# In-Out.net
KiCad netlist of a schematic drawn in Altium Designer
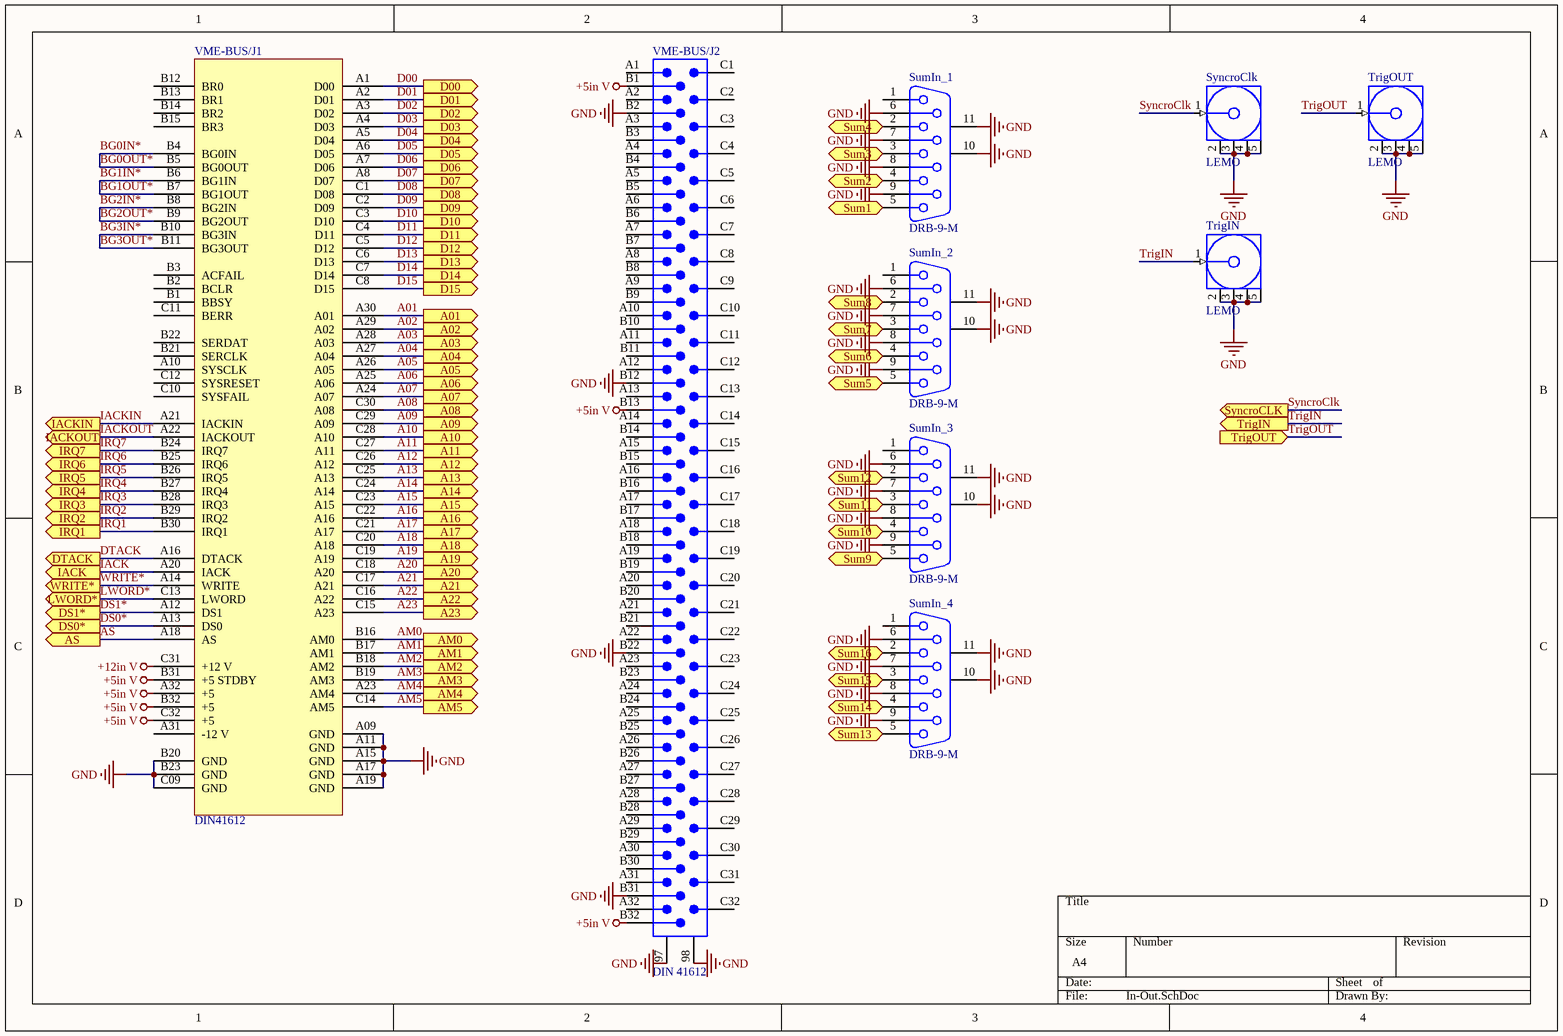
[diagram p0: In-Out.SchDoc]

(export (version "E")
  (design (tool "Eeschema 10.0.6"))
  (components
    (comp (ref "SumIn_1")
      (value "DRB-9-M")
      (footprint "DSUB1.385-2H9")
      (description "Receptacle Assembly, 9 Position, Right Angle")
      (fields (field (name "PUBLISHER") "Altium Limited"))
      (libsource (lib "Miscellaneous Connectors") (part "D Connector 9"))
    )
    (comp (ref "SumIn_2")
      (value "DRB-9-M")
      (footprint "DSUB1.385-2H9")
      (description "Receptacle Assembly, 9 Position, Right Angle")
      (fields (field (name "PUBLISHER") "Altium Limited"))
      (libsource (lib "Miscellaneous Connectors") (part "D Connector 9"))
    )
    (comp (ref "SumIn_3")
      (value "DRB-9-M")
      (footprint "DSUB1.385-2H9")
      (description "Receptacle Assembly, 9 Position, Right Angle")
      (fields (field (name "PUBLISHER") "Altium Limited"))
      (libsource (lib "Miscellaneous Connectors") (part "D Connector 9"))
    )
    (comp (ref "SumIn_4")
      (value "DRB-9-M")
      (footprint "DSUB1.385-2H9")
      (description "Receptacle Assembly, 9 Position, Right Angle")
      (fields (field (name "PUBLISHER") "Altium Limited"))
      (libsource (lib "Miscellaneous Connectors") (part "D Connector 9"))
    )
    (comp (ref "SyncroClk")
      (value "LEMO")
      (footprint "LEMO")
      (fields (field (name "PUBLISHER") "Altium Limited"))
      (libsource (lib "Miscellaneous Connectors") (part "COAX-F"))
    )
    (comp (ref "TrigIN")
      (value "LEMO")
      (footprint "LEMO")
      (fields (field (name "PUBLISHER") "Altium Limited"))
      (libsource (lib "Miscellaneous Connectors") (part "COAX-F"))
    )
    (comp (ref "TrigOUT")
      (value "LEMO")
      (footprint "LEMO")
      (fields (field (name "PUBLISHER") "Altium Limited"))
      (libsource (lib "Miscellaneous Connectors") (part "COAX-F"))
    )
    (comp (ref "VME-BUS/J1")
      (value "DIN41612")
      (footprint "Con DIN 41612:EURO2.54-2H96")
      (libsource (lib "vDevice") (part "VME-P1/J1"))
    )
    (comp (ref "VME-BUS/J2")
      (value "DIN 41612")
      (footprint "EURO2.54-2H96")
      (description "96-Pin Connector (3x32 2.54mm grid)")
      (libsource (lib "*") (part "CNVME96"))
    )
  )
  (nets
    (net (code "1") (name "+5in V") (class "Default")
      (node (ref "VME-BUS/J1") (pin "A32") (pinfunction "+5_A32") (pintype "passive"))
      (node (ref "VME-BUS/J1") (pin "B31") (pinfunction "+5_STDBY_B31") (pintype "passive"))
      (node (ref "VME-BUS/J1") (pin "B32") (pinfunction "+5_B32") (pintype "passive"))
      (node (ref "VME-BUS/J1") (pin "C32") (pinfunction "+5_C32") (pintype "passive"))
      (node (ref "VME-BUS/J2") (pin "B1") (pinfunction "B1_B1") (pintype "passive"))
      (node (ref "VME-BUS/J2") (pin "B13") (pinfunction "B13_B13") (pintype "passive"))
      (node (ref "VME-BUS/J2") (pin "B32") (pinfunction "B32_B32") (pintype "passive"))
    )
    (net (code "2") (name "+12in V") (class "Default")
      (node (ref "VME-BUS/J1") (pin "C31") (pinfunction "+12_V_C31") (pintype "passive"))
    )
    (net (code "3") (name "/A01") (class "Default")
      (node (ref "VME-BUS/J1") (pin "A30") (pinfunction "A01_A30") (pintype "passive"))
    )
    (net (code "4") (name "/A02") (class "Default")
      (node (ref "VME-BUS/J1") (pin "A29") (pinfunction "A02_A29") (pintype "passive"))
    )
    (net (code "5") (name "/A03") (class "Default")
      (node (ref "VME-BUS/J1") (pin "A28") (pinfunction "A03_A28") (pintype "passive"))
    )
    (net (code "6") (name "/A04") (class "Default")
      (node (ref "VME-BUS/J1") (pin "A27") (pinfunction "A04_A27") (pintype "passive"))
    )
    (net (code "7") (name "/A05") (class "Default")
      (node (ref "VME-BUS/J1") (pin "A26") (pinfunction "A05_A26") (pintype "passive"))
    )
    (net (code "8") (name "/A06") (class "Default")
      (node (ref "VME-BUS/J1") (pin "A25") (pinfunction "A06_A25") (pintype "passive"))
    )
    (net (code "9") (name "/A07") (class "Default")
      (node (ref "VME-BUS/J1") (pin "A24") (pinfunction "A07_A24") (pintype "passive"))
    )
    (net (code "10") (name "/A08") (class "Default")
      (node (ref "VME-BUS/J1") (pin "C30") (pinfunction "A08_C30") (pintype "passive"))
    )
    (net (code "11") (name "/A09") (class "Default")
      (node (ref "VME-BUS/J1") (pin "C29") (pinfunction "A09_C29") (pintype "passive"))
    )
    (net (code "12") (name "/A10") (class "Default")
      (node (ref "VME-BUS/J1") (pin "C28") (pinfunction "A10_C28") (pintype "passive"))
    )
    (net (code "13") (name "/A11") (class "Default")
      (node (ref "VME-BUS/J1") (pin "C27") (pinfunction "A11_C27") (pintype "passive"))
    )
    (net (code "14") (name "/A12") (class "Default")
      (node (ref "VME-BUS/J1") (pin "C26") (pinfunction "A12_C26") (pintype "passive"))
    )
    (net (code "15") (name "/A13") (class "Default")
      (node (ref "VME-BUS/J1") (pin "C25") (pinfunction "A13_C25") (pintype "passive"))
    )
    (net (code "16") (name "/A14") (class "Default")
      (node (ref "VME-BUS/J1") (pin "C24") (pinfunction "A14_C24") (pintype "passive"))
    )
    (net (code "17") (name "/A15") (class "Default")
      (node (ref "VME-BUS/J1") (pin "C23") (pinfunction "A15_C23") (pintype "passive"))
    )
    (net (code "18") (name "/A16") (class "Default")
      (node (ref "VME-BUS/J1") (pin "C22") (pinfunction "A16_C22") (pintype "passive"))
    )
    (net (code "19") (name "/A17") (class "Default")
      (node (ref "VME-BUS/J1") (pin "C21") (pinfunction "A17_C21") (pintype "passive"))
    )
    (net (code "20") (name "/A18") (class "Default")
      (node (ref "VME-BUS/J1") (pin "C20") (pinfunction "A18_C20") (pintype "passive"))
    )
    (net (code "21") (name "/A19") (class "Default")
      (node (ref "VME-BUS/J1") (pin "C19") (pinfunction "A19_C19") (pintype "passive"))
    )
    (net (code "22") (name "/A20") (class "Default")
      (node (ref "VME-BUS/J1") (pin "C18") (pinfunction "A20_C18") (pintype "passive"))
    )
    (net (code "23") (name "/A21") (class "Default")
      (node (ref "VME-BUS/J1") (pin "C17") (pinfunction "A21_C17") (pintype "passive"))
    )
    (net (code "24") (name "/A22") (class "Default")
      (node (ref "VME-BUS/J1") (pin "C16") (pinfunction "A22_C16") (pintype "passive"))
    )
    (net (code "25") (name "/A23") (class "Default")
      (node (ref "VME-BUS/J1") (pin "C15") (pinfunction "A23_C15") (pintype "passive"))
    )
    (net (code "26") (name "/AM0") (class "Default")
      (node (ref "VME-BUS/J1") (pin "B16") (pinfunction "AM0_B16") (pintype "passive"))
    )
    (net (code "27") (name "/AM1") (class "Default")
      (node (ref "VME-BUS/J1") (pin "B17") (pinfunction "AM1_B17") (pintype "passive"))
    )
    (net (code "28") (name "/AM2") (class "Default")
      (node (ref "VME-BUS/J1") (pin "B18") (pinfunction "AM2_B18") (pintype "passive"))
    )
    (net (code "29") (name "/AM3") (class "Default")
      (node (ref "VME-BUS/J1") (pin "B19") (pinfunction "AM3_B19") (pintype "passive"))
    )
    (net (code "30") (name "/AM4") (class "Default")
      (node (ref "VME-BUS/J1") (pin "A23") (pinfunction "AM4_A23") (pintype "passive"))
    )
    (net (code "31") (name "/AM5") (class "Default")
      (node (ref "VME-BUS/J1") (pin "C14") (pinfunction "AM5_C14") (pintype "passive"))
    )
    (net (code "32") (name "/AS") (class "Default")
      (node (ref "VME-BUS/J1") (pin "A18") (pinfunction "AS_A18") (pintype "passive"))
    )
    (net (code "33") (name "/BG0IN*") (class "Default")
      (node (ref "VME-BUS/J1") (pin "B4") (pinfunction "BG0IN_B4") (pintype "passive"))
      (node (ref "VME-BUS/J1") (pin "B5") (pinfunction "BG0OUT_B5") (pintype "passive"))
    )
    (net (code "34") (name "/BG1IN*") (class "Default")
      (node (ref "VME-BUS/J1") (pin "B6") (pinfunction "BG1IN_B6") (pintype "passive"))
      (node (ref "VME-BUS/J1") (pin "B7") (pinfunction "BG1OUT_B7") (pintype "passive"))
    )
    (net (code "35") (name "/BG2IN*") (class "Default")
      (node (ref "VME-BUS/J1") (pin "B8") (pinfunction "BG2IN_B8") (pintype "passive"))
      (node (ref "VME-BUS/J1") (pin "B9") (pinfunction "BG2OUT_B9") (pintype "passive"))
    )
    (net (code "36") (name "/BG3IN*") (class "Default")
      (node (ref "VME-BUS/J1") (pin "B10") (pinfunction "BG3IN_B10") (pintype "passive"))
      (node (ref "VME-BUS/J1") (pin "B11") (pinfunction "BG3OUT_B11") (pintype "passive"))
    )
    (net (code "37") (name "/D00") (class "Default")
      (node (ref "VME-BUS/J1") (pin "A1") (pinfunction "D00_A1") (pintype "passive"))
    )
    (net (code "38") (name "/D01") (class "Default")
      (node (ref "VME-BUS/J1") (pin "A2") (pinfunction "D01_A2") (pintype "passive"))
    )
    (net (code "39") (name "/D02") (class "Default")
      (node (ref "VME-BUS/J1") (pin "A3") (pinfunction "D02_A3") (pintype "passive"))
    )
    (net (code "40") (name "/D03") (class "Default")
      (node (ref "VME-BUS/J1") (pin "A4") (pinfunction "D03_A4") (pintype "passive"))
    )
    (net (code "41") (name "/D04") (class "Default")
      (node (ref "VME-BUS/J1") (pin "A5") (pinfunction "D04_A5") (pintype "passive"))
    )
    (net (code "42") (name "/D05") (class "Default")
      (node (ref "VME-BUS/J1") (pin "A6") (pinfunction "D05_A6") (pintype "passive"))
    )
    (net (code "43") (name "/D06") (class "Default")
      (node (ref "VME-BUS/J1") (pin "A7") (pinfunction "D06_A7") (pintype "passive"))
    )
    (net (code "44") (name "/D07") (class "Default")
      (node (ref "VME-BUS/J1") (pin "A8") (pinfunction "D07_A8") (pintype "passive"))
    )
    (net (code "45") (name "/D08") (class "Default")
      (node (ref "VME-BUS/J1") (pin "C1") (pinfunction "D08_C1") (pintype "passive"))
    )
    (net (code "46") (name "/D09") (class "Default")
      (node (ref "VME-BUS/J1") (pin "C2") (pinfunction "D09_C2") (pintype "passive"))
    )
    (net (code "47") (name "/D10") (class "Default")
      (node (ref "VME-BUS/J1") (pin "C3") (pinfunction "D10_C3") (pintype "passive"))
    )
    (net (code "48") (name "/D11") (class "Default")
      (node (ref "VME-BUS/J1") (pin "C4") (pinfunction "D11_C4") (pintype "passive"))
    )
    (net (code "49") (name "/D12") (class "Default")
      (node (ref "VME-BUS/J1") (pin "C5") (pinfunction "D12_C5") (pintype "passive"))
    )
    (net (code "50") (name "/D13") (class "Default")
      (node (ref "VME-BUS/J1") (pin "C6") (pinfunction "D13_C6") (pintype "passive"))
    )
    (net (code "51") (name "/D14") (class "Default")
      (node (ref "VME-BUS/J1") (pin "C7") (pinfunction "D14_C7") (pintype "passive"))
    )
    (net (code "52") (name "/D15") (class "Default")
      (node (ref "VME-BUS/J1") (pin "C8") (pinfunction "D15_C8") (pintype "passive"))
    )
    (net (code "53") (name "/DS0*") (class "Default")
      (node (ref "VME-BUS/J1") (pin "A13") (pinfunction "DS0_A13") (pintype "passive"))
    )
    (net (code "54") (name "/DS1*") (class "Default")
      (node (ref "VME-BUS/J1") (pin "A12") (pinfunction "DS1_A12") (pintype "passive"))
    )
    (net (code "55") (name "/DTACK") (class "Default")
      (node (ref "VME-BUS/J1") (pin "A16") (pinfunction "DTACK_A16") (pintype "passive"))
    )
    (net (code "56") (name "/IACK") (class "Default")
      (node (ref "VME-BUS/J1") (pin "A20") (pinfunction "IACK_A20") (pintype "passive"))
    )
    (net (code "57") (name "/IACKIN") (class "Default")
      (node (ref "VME-BUS/J1") (pin "A21") (pinfunction "IACKIN_A21") (pintype "passive"))
    )
    (net (code "58") (name "/IACKOUT") (class "Default")
      (node (ref "VME-BUS/J1") (pin "A22") (pinfunction "IACKOUT_A22") (pintype "passive"))
    )
    (net (code "59") (name "/IRQ1") (class "Default")
      (node (ref "VME-BUS/J1") (pin "B30") (pinfunction "IRQ1_B30") (pintype "passive"))
    )
    (net (code "60") (name "/IRQ2") (class "Default")
      (node (ref "VME-BUS/J1") (pin "B29") (pinfunction "IRQ2_B29") (pintype "passive"))
    )
    (net (code "61") (name "/IRQ3") (class "Default")
      (node (ref "VME-BUS/J1") (pin "B28") (pinfunction "IRQ3_B28") (pintype "passive"))
    )
    (net (code "62") (name "/IRQ4") (class "Default")
      (node (ref "VME-BUS/J1") (pin "B27") (pinfunction "IRQ4_B27") (pintype "passive"))
    )
    (net (code "63") (name "/IRQ5") (class "Default")
      (node (ref "VME-BUS/J1") (pin "B26") (pinfunction "IRQ5_B26") (pintype "passive"))
    )
    (net (code "64") (name "/IRQ6") (class "Default")
      (node (ref "VME-BUS/J1") (pin "B25") (pinfunction "IRQ6_B25") (pintype "passive"))
    )
    (net (code "65") (name "/IRQ7") (class "Default")
      (node (ref "VME-BUS/J1") (pin "B24") (pinfunction "IRQ7_B24") (pintype "passive"))
    )
    (net (code "66") (name "/LWORD*") (class "Default")
      (node (ref "VME-BUS/J1") (pin "C13") (pinfunction "LWORD_C13") (pintype "passive"))
    )
    (net (code "67") (name "/Sum1") (class "Default")
      (node (ref "SumIn_1") (pin "5") (pinfunction "5_5") (pintype "passive"))
    )
    (net (code "68") (name "/Sum2") (class "Default")
      (node (ref "SumIn_1") (pin "4") (pinfunction "4_4") (pintype "passive"))
    )
    (net (code "69") (name "/Sum3") (class "Default")
      (node (ref "SumIn_1") (pin "3") (pinfunction "3_3") (pintype "passive"))
    )
    (net (code "70") (name "/Sum4") (class "Default")
      (node (ref "SumIn_1") (pin "2") (pinfunction "2_2") (pintype "passive"))
    )
    (net (code "71") (name "/Sum5") (class "Default")
      (node (ref "SumIn_2") (pin "5") (pinfunction "5_5") (pintype "passive"))
    )
    (net (code "72") (name "/Sum6") (class "Default")
      (node (ref "SumIn_2") (pin "4") (pinfunction "4_4") (pintype "passive"))
    )
    (net (code "73") (name "/Sum7") (class "Default")
      (node (ref "SumIn_2") (pin "3") (pinfunction "3_3") (pintype "passive"))
    )
    (net (code "74") (name "/Sum8") (class "Default")
      (node (ref "SumIn_2") (pin "2") (pinfunction "2_2") (pintype "passive"))
    )
    (net (code "75") (name "/Sum9") (class "Default")
      (node (ref "SumIn_3") (pin "5") (pinfunction "5_5") (pintype "passive"))
    )
    (net (code "76") (name "/Sum10") (class "Default")
      (node (ref "SumIn_3") (pin "4") (pinfunction "4_4") (pintype "passive"))
    )
    (net (code "77") (name "/Sum11") (class "Default")
      (node (ref "SumIn_3") (pin "3") (pinfunction "3_3") (pintype "passive"))
    )
    (net (code "78") (name "/Sum12") (class "Default")
      (node (ref "SumIn_3") (pin "2") (pinfunction "2_2") (pintype "passive"))
    )
    (net (code "79") (name "/Sum13") (class "Default")
      (node (ref "SumIn_4") (pin "5") (pinfunction "5_5") (pintype "passive"))
    )
    (net (code "80") (name "/Sum14") (class "Default")
      (node (ref "SumIn_4") (pin "4") (pinfunction "4_4") (pintype "passive"))
    )
    (net (code "81") (name "/Sum15") (class "Default")
      (node (ref "SumIn_4") (pin "3") (pinfunction "3_3") (pintype "passive"))
    )
    (net (code "82") (name "/Sum16") (class "Default")
      (node (ref "SumIn_4") (pin "2") (pinfunction "2_2") (pintype "passive"))
    )
    (net (code "83") (name "/SyncroClk") (class "Default")
      (node (ref "SyncroClk") (pin "1") (pinfunction "Signal_1") (pintype "input"))
    )
    (net (code "84") (name "/TrigIN") (class "Default")
      (node (ref "TrigIN") (pin "1") (pinfunction "Signal_1") (pintype "input"))
    )
    (net (code "85") (name "/TrigOUT") (class "Default")
      (node (ref "TrigOUT") (pin "1") (pinfunction "Signal_1") (pintype "input"))
    )
    (net (code "86") (name "/WRITE*") (class "Default")
      (node (ref "VME-BUS/J1") (pin "A14") (pinfunction "WRITE_A14") (pintype "passive"))
    )
    (net (code "87") (name "GND") (class "Default")
      (node (ref "SumIn_1") (pin "10") (pinfunction "MH1_10") (pintype "passive"))
      (node (ref "SumIn_1") (pin "11") (pinfunction "MH2_11") (pintype "passive"))
      (node (ref "SumIn_1") (pin "6") (pinfunction "6_6") (pintype "passive"))
      (node (ref "SumIn_1") (pin "7") (pinfunction "7_7") (pintype "passive"))
      (node (ref "SumIn_1") (pin "8") (pinfunction "8_8") (pintype "passive"))
      (node (ref "SumIn_1") (pin "9") (pinfunction "9_9") (pintype "passive"))
      (node (ref "SumIn_2") (pin "10") (pinfunction "MH1_10") (pintype "passive"))
      (node (ref "SumIn_2") (pin "11") (pinfunction "MH2_11") (pintype "passive"))
      (node (ref "SumIn_2") (pin "6") (pinfunction "6_6") (pintype "passive"))
      (node (ref "SumIn_2") (pin "7") (pinfunction "7_7") (pintype "passive"))
      (node (ref "SumIn_2") (pin "8") (pinfunction "8_8") (pintype "passive"))
      (node (ref "SumIn_2") (pin "9") (pinfunction "9_9") (pintype "passive"))
      (node (ref "SumIn_3") (pin "10") (pinfunction "MH1_10") (pintype "passive"))
      (node (ref "SumIn_3") (pin "11") (pinfunction "MH2_11") (pintype "passive"))
      (node (ref "SumIn_3") (pin "6") (pinfunction "6_6") (pintype "passive"))
      (node (ref "SumIn_3") (pin "7") (pinfunction "7_7") (pintype "passive"))
      (node (ref "SumIn_3") (pin "8") (pinfunction "8_8") (pintype "passive"))
      (node (ref "SumIn_3") (pin "9") (pinfunction "9_9") (pintype "passive"))
      (node (ref "SumIn_4") (pin "10") (pinfunction "MH1_10") (pintype "passive"))
      (node (ref "SumIn_4") (pin "11") (pinfunction "MH2_11") (pintype "passive"))
      (node (ref "SumIn_4") (pin "6") (pinfunction "6_6") (pintype "passive"))
      (node (ref "SumIn_4") (pin "7") (pinfunction "7_7") (pintype "passive"))
      (node (ref "SumIn_4") (pin "8") (pinfunction "8_8") (pintype "passive"))
      (node (ref "SumIn_4") (pin "9") (pinfunction "9_9") (pintype "passive"))
      (node (ref "SyncroClk") (pin "2") (pinfunction "GND_2") (pintype "power_in"))
      (node (ref "SyncroClk") (pin "3") (pinfunction "GND_3") (pintype "power_in"))
      (node (ref "SyncroClk") (pin "4") (pinfunction "GND_4") (pintype "power_in"))
      (node (ref "SyncroClk") (pin "5") (pinfunction "GND_5") (pintype "power_in"))
      (node (ref "TrigIN") (pin "2") (pinfunction "GND_2") (pintype "power_in"))
      (node (ref "TrigIN") (pin "3") (pinfunction "GND_3") (pintype "power_in"))
      (node (ref "TrigIN") (pin "4") (pinfunction "GND_4") (pintype "power_in"))
      (node (ref "TrigIN") (pin "5") (pinfunction "GND_5") (pintype "power_in"))
      (node (ref "TrigOUT") (pin "2") (pinfunction "GND_2") (pintype "power_in"))
      (node (ref "TrigOUT") (pin "3") (pinfunction "GND_3") (pintype "power_in"))
      (node (ref "TrigOUT") (pin "4") (pinfunction "GND_4") (pintype "power_in"))
      (node (ref "TrigOUT") (pin "5") (pinfunction "GND_5") (pintype "power_in"))
      (node (ref "VME-BUS/J1") (pin "A09") (pinfunction "GND_A09") (pintype "passive"))
      (node (ref "VME-BUS/J1") (pin "A11") (pinfunction "GND_A11") (pintype "passive"))
      (node (ref "VME-BUS/J1") (pin "A15") (pinfunction "GND_A15") (pintype "passive"))
      (node (ref "VME-BUS/J1") (pin "A17") (pinfunction "GND_A17") (pintype "passive"))
      (node (ref "VME-BUS/J1") (pin "A19") (pinfunction "GND_A19") (pintype "passive"))
      (node (ref "VME-BUS/J1") (pin "B20") (pinfunction "GND_B20") (pintype "passive"))
      (node (ref "VME-BUS/J1") (pin "B23") (pinfunction "GND_B23") (pintype "passive"))
      (node (ref "VME-BUS/J1") (pin "C09") (pinfunction "GND_C09") (pintype "passive"))
      (node (ref "VME-BUS/J2") (pin "97") (pinfunction "97_97") (pintype "passive"))
      (node (ref "VME-BUS/J2") (pin "98") (pinfunction "98_98") (pintype "passive"))
      (node (ref "VME-BUS/J2") (pin "B12") (pinfunction "B12_B12") (pintype "passive"))
      (node (ref "VME-BUS/J2") (pin "B2") (pinfunction "B2_B2") (pintype "passive"))
      (node (ref "VME-BUS/J2") (pin "B22") (pinfunction "B22_B22") (pintype "passive"))
      (node (ref "VME-BUS/J2") (pin "B31") (pinfunction "B31_B31") (pintype "passive"))
    )
    (net (code "88") (name "unconnected-(SumIn_1-Pad1)") (class "Default")
      (node (ref "SumIn_1") (pin "1") (pinfunction "1_1") (pintype "passive"))
    )
    (net (code "89") (name "unconnected-(SumIn_2-Pad1)") (class "Default")
      (node (ref "SumIn_2") (pin "1") (pinfunction "1_1") (pintype "passive"))
    )
    (net (code "90") (name "unconnected-(SumIn_3-Pad1)") (class "Default")
      (node (ref "SumIn_3") (pin "1") (pinfunction "1_1") (pintype "passive"))
    )
    (net (code "91") (name "unconnected-(SumIn_4-Pad1)") (class "Default")
      (node (ref "SumIn_4") (pin "1") (pinfunction "1_1") (pintype "passive"))
    )
    (net (code "92") (name "unconnected-(VME-BUS/J1--12_V-PadA31)") (class "Default")
      (node (ref "VME-BUS/J1") (pin "A31") (pinfunction "-12_V_A31") (pintype "passive"))
    )
    (net (code "93") (name "unconnected-(VME-BUS/J1-ACFAIL-PadB3)") (class "Default")
      (node (ref "VME-BUS/J1") (pin "B3") (pinfunction "ACFAIL_B3") (pintype "passive"))
    )
    (net (code "94") (name "unconnected-(VME-BUS/J1-BBSY-PadB1)") (class "Default")
      (node (ref "VME-BUS/J1") (pin "B1") (pinfunction "BBSY_B1") (pintype "passive"))
    )
    (net (code "95") (name "unconnected-(VME-BUS/J1-BCLR-PadB2)") (class "Default")
      (node (ref "VME-BUS/J1") (pin "B2") (pinfunction "BCLR_B2") (pintype "passive"))
    )
    (net (code "96") (name "unconnected-(VME-BUS/J1-BERR-PadC11)") (class "Default")
      (node (ref "VME-BUS/J1") (pin "C11") (pinfunction "BERR_C11") (pintype "passive"))
    )
    (net (code "97") (name "unconnected-(VME-BUS/J1-BR0-PadB12)") (class "Default")
      (node (ref "VME-BUS/J1") (pin "B12") (pinfunction "BR0_B12") (pintype "passive"))
    )
    (net (code "98") (name "unconnected-(VME-BUS/J1-BR1-PadB13)") (class "Default")
      (node (ref "VME-BUS/J1") (pin "B13") (pinfunction "BR1_B13") (pintype "passive"))
    )
    (net (code "99") (name "unconnected-(VME-BUS/J1-BR2-PadB14)") (class "Default")
      (node (ref "VME-BUS/J1") (pin "B14") (pinfunction "BR2_B14") (pintype "passive"))
    )
    (net (code "100") (name "unconnected-(VME-BUS/J1-BR3-PadB15)") (class "Default")
      (node (ref "VME-BUS/J1") (pin "B15") (pinfunction "BR3_B15") (pintype "passive"))
    )
    (net (code "101") (name "unconnected-(VME-BUS/J1-SERCLK-PadB21)") (class "Default")
      (node (ref "VME-BUS/J1") (pin "B21") (pinfunction "SERCLK_B21") (pintype "passive"))
    )
    (net (code "102") (name "unconnected-(VME-BUS/J1-SERDAT-PadB22)") (class "Default")
      (node (ref "VME-BUS/J1") (pin "B22") (pinfunction "SERDAT_B22") (pintype "passive"))
    )
    (net (code "103") (name "unconnected-(VME-BUS/J1-SYSCLK-PadA10)") (class "Default")
      (node (ref "VME-BUS/J1") (pin "A10") (pinfunction "SYSCLK_A10") (pintype "passive"))
    )
    (net (code "104") (name "unconnected-(VME-BUS/J1-SYSFAIL-PadC10)") (class "Default")
      (node (ref "VME-BUS/J1") (pin "C10") (pinfunction "SYSFAIL_C10") (pintype "passive"))
    )
    (net (code "105") (name "unconnected-(VME-BUS/J1-SYSRESET-PadC12)") (class "Default")
      (node (ref "VME-BUS/J1") (pin "C12") (pinfunction "SYSRESET_C12") (pintype "passive"))
    )
    (net (code "106") (name "unconnected-(VME-BUS/J2-PadA1)") (class "Default")
      (node (ref "VME-BUS/J2") (pin "A1") (pinfunction "A1_A1") (pintype "passive"))
    )
    (net (code "107") (name "unconnected-(VME-BUS/J2-PadA2)") (class "Default")
      (node (ref "VME-BUS/J2") (pin "A2") (pinfunction "A2_A2") (pintype "passive"))
    )
    (net (code "108") (name "unconnected-(VME-BUS/J2-PadA3)") (class "Default")
      (node (ref "VME-BUS/J2") (pin "A3") (pinfunction "A3_A3") (pintype "passive"))
    )
    (net (code "109") (name "unconnected-(VME-BUS/J2-PadA4)") (class "Default")
      (node (ref "VME-BUS/J2") (pin "A4") (pinfunction "A4_A4") (pintype "passive"))
    )
    (net (code "110") (name "unconnected-(VME-BUS/J2-PadA5)") (class "Default")
      (node (ref "VME-BUS/J2") (pin "A5") (pinfunction "A5_A5") (pintype "passive"))
    )
    (net (code "111") (name "unconnected-(VME-BUS/J2-PadA6)") (class "Default")
      (node (ref "VME-BUS/J2") (pin "A6") (pinfunction "A6_A6") (pintype "passive"))
    )
    (net (code "112") (name "unconnected-(VME-BUS/J2-PadA7)") (class "Default")
      (node (ref "VME-BUS/J2") (pin "A7") (pinfunction "A7_A7") (pintype "passive"))
    )
    (net (code "113") (name "unconnected-(VME-BUS/J2-PadA8)") (class "Default")
      (node (ref "VME-BUS/J2") (pin "A8") (pinfunction "A8_A8") (pintype "passive"))
    )
    (net (code "114") (name "unconnected-(VME-BUS/J2-PadA9)") (class "Default")
      (node (ref "VME-BUS/J2") (pin "A9") (pinfunction "A9_A9") (pintype "passive"))
    )
    (net (code "115") (name "unconnected-(VME-BUS/J2-PadA10)") (class "Default")
      (node (ref "VME-BUS/J2") (pin "A10") (pinfunction "A10_A10") (pintype "passive"))
    )
    (net (code "116") (name "unconnected-(VME-BUS/J2-PadA11)") (class "Default")
      (node (ref "VME-BUS/J2") (pin "A11") (pinfunction "A11_A11") (pintype "passive"))
    )
    (net (code "117") (name "unconnected-(VME-BUS/J2-PadA12)") (class "Default")
      (node (ref "VME-BUS/J2") (pin "A12") (pinfunction "A12_A12") (pintype "passive"))
    )
    (net (code "118") (name "unconnected-(VME-BUS/J2-PadA13)") (class "Default")
      (node (ref "VME-BUS/J2") (pin "A13") (pinfunction "A13_A13") (pintype "passive"))
    )
    (net (code "119") (name "unconnected-(VME-BUS/J2-PadA14)") (class "Default")
      (node (ref "VME-BUS/J2") (pin "A14") (pinfunction "A14_A14") (pintype "passive"))
    )
    (net (code "120") (name "unconnected-(VME-BUS/J2-PadA15)") (class "Default")
      (node (ref "VME-BUS/J2") (pin "A15") (pinfunction "A15_A15") (pintype "passive"))
    )
    (net (code "121") (name "unconnected-(VME-BUS/J2-PadA16)") (class "Default")
      (node (ref "VME-BUS/J2") (pin "A16") (pinfunction "A16_A16") (pintype "passive"))
    )
    (net (code "122") (name "unconnected-(VME-BUS/J2-PadA17)") (class "Default")
      (node (ref "VME-BUS/J2") (pin "A17") (pinfunction "A17_A17") (pintype "passive"))
    )
    (net (code "123") (name "unconnected-(VME-BUS/J2-PadA18)") (class "Default")
      (node (ref "VME-BUS/J2") (pin "A18") (pinfunction "A18_A18") (pintype "passive"))
    )
    (net (code "124") (name "unconnected-(VME-BUS/J2-PadA19)") (class "Default")
      (node (ref "VME-BUS/J2") (pin "A19") (pinfunction "A19_A19") (pintype "passive"))
    )
    (net (code "125") (name "unconnected-(VME-BUS/J2-PadA20)") (class "Default")
      (node (ref "VME-BUS/J2") (pin "A20") (pinfunction "A20_A20") (pintype "passive"))
    )
    (net (code "126") (name "unconnected-(VME-BUS/J2-PadA21)") (class "Default")
      (node (ref "VME-BUS/J2") (pin "A21") (pinfunction "A21_A21") (pintype "passive"))
    )
    (net (code "127") (name "unconnected-(VME-BUS/J2-PadA22)") (class "Default")
      (node (ref "VME-BUS/J2") (pin "A22") (pinfunction "A22_A22") (pintype "passive"))
    )
    (net (code "128") (name "unconnected-(VME-BUS/J2-PadA23)") (class "Default")
      (node (ref "VME-BUS/J2") (pin "A23") (pinfunction "A23_A23") (pintype "passive"))
    )
    (net (code "129") (name "unconnected-(VME-BUS/J2-PadA24)") (class "Default")
      (node (ref "VME-BUS/J2") (pin "A24") (pinfunction "A24_A24") (pintype "passive"))
    )
    (net (code "130") (name "unconnected-(VME-BUS/J2-PadA25)") (class "Default")
      (node (ref "VME-BUS/J2") (pin "A25") (pinfunction "A25_A25") (pintype "passive"))
    )
    (net (code "131") (name "unconnected-(VME-BUS/J2-PadA26)") (class "Default")
      (node (ref "VME-BUS/J2") (pin "A26") (pinfunction "A26_A26") (pintype "passive"))
    )
    (net (code "132") (name "unconnected-(VME-BUS/J2-PadA27)") (class "Default")
      (node (ref "VME-BUS/J2") (pin "A27") (pinfunction "A27_A27") (pintype "passive"))
    )
    (net (code "133") (name "unconnected-(VME-BUS/J2-PadA28)") (class "Default")
      (node (ref "VME-BUS/J2") (pin "A28") (pinfunction "A28_A28") (pintype "passive"))
    )
    (net (code "134") (name "unconnected-(VME-BUS/J2-PadA29)") (class "Default")
      (node (ref "VME-BUS/J2") (pin "A29") (pinfunction "A29_A29") (pintype "passive"))
    )
    (net (code "135") (name "unconnected-(VME-BUS/J2-PadA30)") (class "Default")
      (node (ref "VME-BUS/J2") (pin "A30") (pinfunction "A30_A30") (pintype "passive"))
    )
    (net (code "136") (name "unconnected-(VME-BUS/J2-PadA31)") (class "Default")
      (node (ref "VME-BUS/J2") (pin "A31") (pinfunction "A31_A31") (pintype "passive"))
    )
    (net (code "137") (name "unconnected-(VME-BUS/J2-PadA32)") (class "Default")
      (node (ref "VME-BUS/J2") (pin "A32") (pinfunction "A32_A32") (pintype "passive"))
    )
    (net (code "138") (name "unconnected-(VME-BUS/J2-PadB3)") (class "Default")
      (node (ref "VME-BUS/J2") (pin "B3") (pinfunction "B3_B3") (pintype "passive"))
    )
    (net (code "139") (name "unconnected-(VME-BUS/J2-PadB4)") (class "Default")
      (node (ref "VME-BUS/J2") (pin "B4") (pinfunction "B4_B4") (pintype "passive"))
    )
    (net (code "140") (name "unconnected-(VME-BUS/J2-PadB5)") (class "Default")
      (node (ref "VME-BUS/J2") (pin "B5") (pinfunction "B5_B5") (pintype "passive"))
    )
    (net (code "141") (name "unconnected-(VME-BUS/J2-PadB6)") (class "Default")
      (node (ref "VME-BUS/J2") (pin "B6") (pinfunction "B6_B6") (pintype "passive"))
    )
    (net (code "142") (name "unconnected-(VME-BUS/J2-PadB7)") (class "Default")
      (node (ref "VME-BUS/J2") (pin "B7") (pinfunction "B7_B7") (pintype "passive"))
    )
    (net (code "143") (name "unconnected-(VME-BUS/J2-PadB8)") (class "Default")
      (node (ref "VME-BUS/J2") (pin "B8") (pinfunction "B8_B8") (pintype "passive"))
    )
    (net (code "144") (name "unconnected-(VME-BUS/J2-PadB9)") (class "Default")
      (node (ref "VME-BUS/J2") (pin "B9") (pinfunction "B9_B9") (pintype "passive"))
    )
    (net (code "145") (name "unconnected-(VME-BUS/J2-PadB10)") (class "Default")
      (node (ref "VME-BUS/J2") (pin "B10") (pinfunction "B10_B10") (pintype "passive"))
    )
    (net (code "146") (name "unconnected-(VME-BUS/J2-PadB11)") (class "Default")
      (node (ref "VME-BUS/J2") (pin "B11") (pinfunction "B11_B11") (pintype "passive"))
    )
    (net (code "147") (name "unconnected-(VME-BUS/J2-PadB14)") (class "Default")
      (node (ref "VME-BUS/J2") (pin "B14") (pinfunction "B14_B14") (pintype "passive"))
    )
    (net (code "148") (name "unconnected-(VME-BUS/J2-PadB15)") (class "Default")
      (node (ref "VME-BUS/J2") (pin "B15") (pinfunction "B15_B15") (pintype "passive"))
    )
    (net (code "149") (name "unconnected-(VME-BUS/J2-PadB16)") (class "Default")
      (node (ref "VME-BUS/J2") (pin "B16") (pinfunction "B16_B16") (pintype "passive"))
    )
    (net (code "150") (name "unconnected-(VME-BUS/J2-PadB17)") (class "Default")
      (node (ref "VME-BUS/J2") (pin "B17") (pinfunction "B17_B17") (pintype "passive"))
    )
    (net (code "151") (name "unconnected-(VME-BUS/J2-PadB18)") (class "Default")
      (node (ref "VME-BUS/J2") (pin "B18") (pinfunction "B18_B18") (pintype "passive"))
    )
    (net (code "152") (name "unconnected-(VME-BUS/J2-PadB19)") (class "Default")
      (node (ref "VME-BUS/J2") (pin "B19") (pinfunction "B19_B19") (pintype "passive"))
    )
    (net (code "153") (name "unconnected-(VME-BUS/J2-PadB20)") (class "Default")
      (node (ref "VME-BUS/J2") (pin "B20") (pinfunction "B20_B20") (pintype "passive"))
    )
    (net (code "154") (name "unconnected-(VME-BUS/J2-PadB21)") (class "Default")
      (node (ref "VME-BUS/J2") (pin "B21") (pinfunction "B21_B21") (pintype "passive"))
    )
    (net (code "155") (name "unconnected-(VME-BUS/J2-PadB23)") (class "Default")
      (node (ref "VME-BUS/J2") (pin "B23") (pinfunction "B23_B23") (pintype "passive"))
    )
    (net (code "156") (name "unconnected-(VME-BUS/J2-PadB24)") (class "Default")
      (node (ref "VME-BUS/J2") (pin "B24") (pinfunction "B24_B24") (pintype "passive"))
    )
    (net (code "157") (name "unconnected-(VME-BUS/J2-PadB25)") (class "Default")
      (node (ref "VME-BUS/J2") (pin "B25") (pinfunction "B25_B25") (pintype "passive"))
    )
    (net (code "158") (name "unconnected-(VME-BUS/J2-PadB26)") (class "Default")
      (node (ref "VME-BUS/J2") (pin "B26") (pinfunction "B26_B26") (pintype "passive"))
    )
    (net (code "159") (name "unconnected-(VME-BUS/J2-PadB27)") (class "Default")
      (node (ref "VME-BUS/J2") (pin "B27") (pinfunction "B27_B27") (pintype "passive"))
    )
    (net (code "160") (name "unconnected-(VME-BUS/J2-PadB28)") (class "Default")
      (node (ref "VME-BUS/J2") (pin "B28") (pinfunction "B28_B28") (pintype "passive"))
    )
    (net (code "161") (name "unconnected-(VME-BUS/J2-PadB29)") (class "Default")
      (node (ref "VME-BUS/J2") (pin "B29") (pinfunction "B29_B29") (pintype "passive"))
    )
    (net (code "162") (name "unconnected-(VME-BUS/J2-PadB30)") (class "Default")
      (node (ref "VME-BUS/J2") (pin "B30") (pinfunction "B30_B30") (pintype "passive"))
    )
    (net (code "163") (name "unconnected-(VME-BUS/J2-PadC1)") (class "Default")
      (node (ref "VME-BUS/J2") (pin "C1") (pinfunction "C1_C1") (pintype "passive"))
    )
    (net (code "164") (name "unconnected-(VME-BUS/J2-PadC2)") (class "Default")
      (node (ref "VME-BUS/J2") (pin "C2") (pinfunction "C2_C2") (pintype "passive"))
    )
    (net (code "165") (name "unconnected-(VME-BUS/J2-PadC3)") (class "Default")
      (node (ref "VME-BUS/J2") (pin "C3") (pinfunction "C3_C3") (pintype "passive"))
    )
    (net (code "166") (name "unconnected-(VME-BUS/J2-PadC4)") (class "Default")
      (node (ref "VME-BUS/J2") (pin "C4") (pinfunction "C4_C4") (pintype "passive"))
    )
    (net (code "167") (name "unconnected-(VME-BUS/J2-PadC5)") (class "Default")
      (node (ref "VME-BUS/J2") (pin "C5") (pinfunction "C5_C5") (pintype "passive"))
    )
    (net (code "168") (name "unconnected-(VME-BUS/J2-PadC6)") (class "Default")
      (node (ref "VME-BUS/J2") (pin "C6") (pinfunction "C6_C6") (pintype "passive"))
    )
    (net (code "169") (name "unconnected-(VME-BUS/J2-PadC7)") (class "Default")
      (node (ref "VME-BUS/J2") (pin "C7") (pinfunction "C7_C7") (pintype "passive"))
    )
    (net (code "170") (name "unconnected-(VME-BUS/J2-PadC8)") (class "Default")
      (node (ref "VME-BUS/J2") (pin "C8") (pinfunction "C8_C8") (pintype "passive"))
    )
    (net (code "171") (name "unconnected-(VME-BUS/J2-PadC9)") (class "Default")
      (node (ref "VME-BUS/J2") (pin "C9") (pinfunction "C9_C9") (pintype "passive"))
    )
    (net (code "172") (name "unconnected-(VME-BUS/J2-PadC10)") (class "Default")
      (node (ref "VME-BUS/J2") (pin "C10") (pinfunction "C10_C10") (pintype "passive"))
    )
    (net (code "173") (name "unconnected-(VME-BUS/J2-PadC11)") (class "Default")
      (node (ref "VME-BUS/J2") (pin "C11") (pinfunction "C11_C11") (pintype "passive"))
    )
    (net (code "174") (name "unconnected-(VME-BUS/J2-PadC12)") (class "Default")
      (node (ref "VME-BUS/J2") (pin "C12") (pinfunction "C12_C12") (pintype "passive"))
    )
    (net (code "175") (name "unconnected-(VME-BUS/J2-PadC13)") (class "Default")
      (node (ref "VME-BUS/J2") (pin "C13") (pinfunction "C13_C13") (pintype "passive"))
    )
    (net (code "176") (name "unconnected-(VME-BUS/J2-PadC14)") (class "Default")
      (node (ref "VME-BUS/J2") (pin "C14") (pinfunction "C14_C14") (pintype "passive"))
    )
    (net (code "177") (name "unconnected-(VME-BUS/J2-PadC15)") (class "Default")
      (node (ref "VME-BUS/J2") (pin "C15") (pinfunction "C15_C15") (pintype "passive"))
    )
    (net (code "178") (name "unconnected-(VME-BUS/J2-PadC16)") (class "Default")
      (node (ref "VME-BUS/J2") (pin "C16") (pinfunction "C16_C16") (pintype "passive"))
    )
    (net (code "179") (name "unconnected-(VME-BUS/J2-PadC17)") (class "Default")
      (node (ref "VME-BUS/J2") (pin "C17") (pinfunction "C17_C17") (pintype "passive"))
    )
    (net (code "180") (name "unconnected-(VME-BUS/J2-PadC18)") (class "Default")
      (node (ref "VME-BUS/J2") (pin "C18") (pinfunction "C18_C18") (pintype "passive"))
    )
    (net (code "181") (name "unconnected-(VME-BUS/J2-PadC19)") (class "Default")
      (node (ref "VME-BUS/J2") (pin "C19") (pinfunction "C19_C19") (pintype "passive"))
    )
    (net (code "182") (name "unconnected-(VME-BUS/J2-PadC20)") (class "Default")
      (node (ref "VME-BUS/J2") (pin "C20") (pinfunction "C20_C20") (pintype "passive"))
    )
    (net (code "183") (name "unconnected-(VME-BUS/J2-PadC21)") (class "Default")
      (node (ref "VME-BUS/J2") (pin "C21") (pinfunction "C21_C21") (pintype "passive"))
    )
    (net (code "184") (name "unconnected-(VME-BUS/J2-PadC22)") (class "Default")
      (node (ref "VME-BUS/J2") (pin "C22") (pinfunction "C22_C22") (pintype "passive"))
    )
    (net (code "185") (name "unconnected-(VME-BUS/J2-PadC23)") (class "Default")
      (node (ref "VME-BUS/J2") (pin "C23") (pinfunction "C23_C23") (pintype "passive"))
    )
    (net (code "186") (name "unconnected-(VME-BUS/J2-PadC24)") (class "Default")
      (node (ref "VME-BUS/J2") (pin "C24") (pinfunction "C24_C24") (pintype "passive"))
    )
    (net (code "187") (name "unconnected-(VME-BUS/J2-PadC25)") (class "Default")
      (node (ref "VME-BUS/J2") (pin "C25") (pinfunction "C25_C25") (pintype "passive"))
    )
    (net (code "188") (name "unconnected-(VME-BUS/J2-PadC26)") (class "Default")
      (node (ref "VME-BUS/J2") (pin "C26") (pinfunction "C26_C26") (pintype "passive"))
    )
    (net (code "189") (name "unconnected-(VME-BUS/J2-PadC27)") (class "Default")
      (node (ref "VME-BUS/J2") (pin "C27") (pinfunction "C27_C27") (pintype "passive"))
    )
    (net (code "190") (name "unconnected-(VME-BUS/J2-PadC28)") (class "Default")
      (node (ref "VME-BUS/J2") (pin "C28") (pinfunction "C28_C28") (pintype "passive"))
    )
    (net (code "191") (name "unconnected-(VME-BUS/J2-PadC29)") (class "Default")
      (node (ref "VME-BUS/J2") (pin "C29") (pinfunction "C29_C29") (pintype "passive"))
    )
    (net (code "192") (name "unconnected-(VME-BUS/J2-PadC30)") (class "Default")
      (node (ref "VME-BUS/J2") (pin "C30") (pinfunction "C30_C30") (pintype "passive"))
    )
    (net (code "193") (name "unconnected-(VME-BUS/J2-PadC31)") (class "Default")
      (node (ref "VME-BUS/J2") (pin "C31") (pinfunction "C31_C31") (pintype "passive"))
    )
    (net (code "194") (name "unconnected-(VME-BUS/J2-PadC32)") (class "Default")
      (node (ref "VME-BUS/J2") (pin "C32") (pinfunction "C32_C32") (pintype "passive"))
    )
  )
)
